# 12.net
KiCad netlist of a schematic drawn in Altium Designer
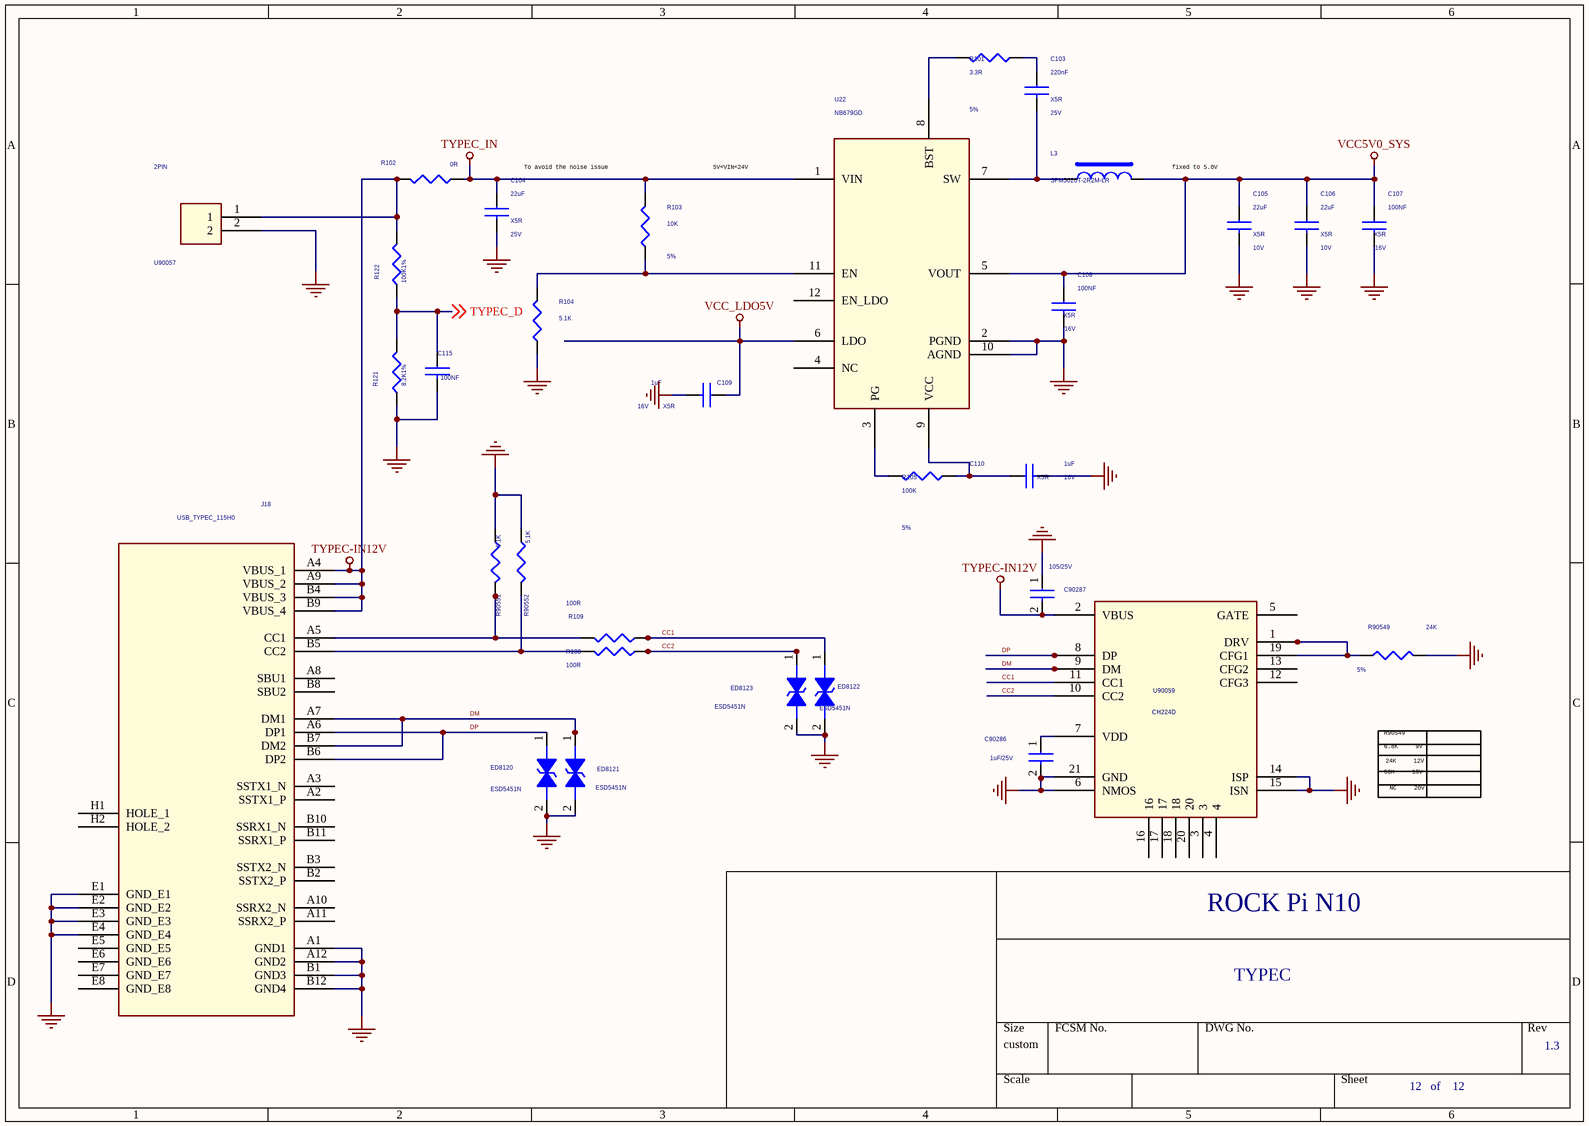
[diagram p0: 12.SchDoc]

(export (version "E")
  (design (tool "Eeschema 10.0.6"))
  (components
    (comp (ref "C103")
      (value "220nF")
      (footprint "C0402")
      (description "cap,220.00nF,+/-10%,25V,X5R,C0402")
      (fields
        (field (name "DIELECTRIC") "X5R")
        (field (name "VOLTAGE") "25V")
        (field (name "MANUFACTURER") "TDK")
        (field (name "TOLERANCE") "10%")
        (field (name "CREATED BY") "JJJ")
      )
      (libsource (lib "*") (part "CAP NP_2"))
    )
    (comp (ref "C104")
      (value "22uF")
      (footprint "C0805")
      (description "cap,10.00uF,+/-10%,16V,X5R,C0805")
      (fields
        (field (name "DIELECTRIC") "X5R")
        (field (name "VOLTAGE") "25V")
        (field (name "TOLERANCE") "10%")
        (field (name "MANUFACTURER") "TDK")
        (field (name "CREATED BY") "JJJ")
      )
      (libsource (lib "*") (part "CAP NP_2"))
    )
    (comp (ref "C105")
      (value "22uF")
      (footprint "C0603")
      (description "cap,22.00uF,+/-10%,10V,X5R,C0805")
      (fields
        (field (name "DIELECTRIC") "X5R")
        (field (name "VOLTAGE") "10V")
        (field (name "TOLERANCE") "10%")
        (field (name "MANUFACTURER") "TDK")
        (field (name "CREATED BY") "JJJ")
      )
      (libsource (lib "*") (part "CAP NP_2"))
    )
    (comp (ref "C106")
      (value "22uF")
      (footprint "C0603")
      (description "cap,22.00uF,+/-10%,10V,X5R,C0805")
      (fields
        (field (name "DIELECTRIC") "X5R")
        (field (name "VOLTAGE") "10V")
        (field (name "TOLERANCE") "10%")
        (field (name "MANUFACTURER") "TDK")
        (field (name "CREATED BY") "JJJ")
      )
      (libsource (lib "*") (part "CAP NP_2"))
    )
    (comp (ref "C107")
      (value "100NF")
      (footprint "C0402")
      (description "cap,100.00nF,+/-10%,16V,X5R,C0402")
      (fields
        (field (name "DIELECTRIC") "X5R")
        (field (name "VOLTAGE") "16V")
        (field (name "MANUFACTURER") "TDK")
        (field (name "TOLERANCE") "10%")
        (field (name "CREATED BY") "JJJ")
      )
      (libsource (lib "*") (part "CAP NP_2"))
    )
    (comp (ref "C108")
      (value "100NF")
      (footprint "C0402")
      (description "cap,100.00nF,+/-10%,16V,X5R,C0402")
      (fields
        (field (name "DIELECTRIC") "X5R")
        (field (name "VOLTAGE") "16V")
        (field (name "TOLERANCE") "10%")
        (field (name "MANUFACTURER") "TDK")
        (field (name "CREATED BY") "JJJ")
      )
      (libsource (lib "*") (part "CAP NP_2"))
    )
    (comp (ref "C109")
      (value "1uF")
      (footprint "C0402")
      (description "cap,1.00uF,+/-10%,16V,X5R,C0402")
      (fields
        (field (name "DIELECTRIC") "X5R")
        (field (name "VOLTAGE") "16V")
        (field (name "MANUFACTURER") "TDK")
        (field (name "TOLERANCE") "10%")
        (field (name "CREATED BY") "JJJ")
      )
      (libsource (lib "*") (part "CAP NP_2"))
    )
    (comp (ref "C110")
      (value "1uF")
      (footprint "C0402")
      (description "cap,1.00uF,+/-10%,16V,X5R,C0402")
      (fields
        (field (name "DIELECTRIC") "X5R")
        (field (name "VOLTAGE") "16V")
        (field (name "TOLERANCE") "10%")
        (field (name "MANUFACTURER") "TDK")
        (field (name "CREATED BY") "JJJ")
      )
      (libsource (lib "*") (part "CAP NP_2"))
    )
    (comp (ref "C115")
      (value "100NF")
      (footprint "C0402")
      (description "cap,100.00nF,+/-10%,16V,X5R,C0402")
      (fields
        (field (name "VOLTAGE") "16V")
        (field (name "MANUFACTURER") "TDK")
        (field (name "CREATED BY") "JJJ")
      )
      (libsource (lib "*") (part "CAP NP_2"))
    )
    (comp (ref "C90286")
      (value "1uF/25V")
      (footprint "C0603")
      (description "cap,1.00uF,+/-10%,16V,X5R,C0402")
      (fields
        (field (name "VOLTAGE") "16V")
        (field (name "MANUFACTURER") "TDK")
        (field (name "CREATED BY") "JJJ")
      )
      (libsource (lib "*") (part "CAP NP"))
    )
    (comp (ref "C90287")
      (value "105/25V")
      (footprint "C0402")
      (description "cap,1.00uF,+/-10%,16V,X5R,C0402")
      (fields
        (field (name "VOLTAGE") "25V")
        (field (name "TOLERANCE") "10%")
        (field (name "CREATED BY") "JJJ")
      )
      (libsource (lib "*") (part "CAP NP"))
    )
    (comp (ref "ED8120")
      (value "ESD5451N")
      (footprint "E0402N")
      (description "1-Line, Bi-directional, Transient Voltage Suppressors.17.5pF.")
      (fields (field (name "MANUFACTURER") "WillSemi(韦尔半导体)") (field (name "CREATED BY") "JJJ"))
      (libsource (lib "*") (part "DIODE BI_DIR TRIG"))
    )
    (comp (ref "ED8121")
      (value "ESD5451N")
      (footprint "E0402N")
      (description "1-Line, Bi-directional, Transient Voltage Suppressors.17.5pF.")
      (fields (field (name "MANUFACTURER") "WillSemi(韦尔半导体)") (field (name "CREATED BY") "JJJ"))
      (libsource (lib "*") (part "DIODE BI_DIR TRIG"))
    )
    (comp (ref "ED8122")
      (value "ESD5451N")
      (footprint "E0402N")
      (description "1-Line, Bi-directional, Transient Voltage Suppressors.17.5pF.")
      (fields (field (name "MANUFACTURER") "WillSemi(韦尔半导体)") (field (name "CREATED BY") "JJJ"))
      (libsource (lib "*") (part "DIODE BI_DIR TRIG"))
    )
    (comp (ref "ED8123")
      (value "ESD5451N")
      (footprint "E0402N")
      (description "1-Line, Bi-directional, Transient Voltage Suppressors.17.5pF.")
      (fields (field (name "MANUFACTURER") "WillSemi(韦尔半导体)") (field (name "CREATED BY") "JJJ"))
      (libsource (lib "*") (part "DIODE BI_DIR TRIG"))
    )
    (comp (ref "J18")
      (value "USB_TYPEC_115H0")
      (footprint "TYPEC-16PIN-GY")
      (description "USB Type-C 连接座")
      (fields (field (name "MANUFACTURER") "泰科") (field (name "CREATED BY") "JJJ"))
      (libsource (lib "*") (part "USB31_TYPE_C"))
    )
    (comp (ref "L3")
      (value "SPM5020T-2R2M-LR")
      (footprint "IND-5020")
      (libsource (lib "*") (part "INDUCTORS OF FERRITE"))
    )
    (comp (ref "R101")
      (value "3.3R")
      (footprint "R0402")
      (description "通用厚膜电阻,3R3,+/-5%,R0402,1/16W.")
      (fields
        (field (name "TOLERANCE") "5%")
        (field (name "MANUFACTURER") "YAGEO")
        (field (name "CREATED BY") "YTL")
      )
      (libsource (lib "*") (part "RESISTOR_3"))
    )
    (comp (ref "R102")
      (value "0R")
      (footprint "R1206")
      (description "SMD  1206  0R  1/4W  ±1%  ROHS")
      (libsource (lib "*") (part "R_0"))
    )
    (comp (ref "R103")
      (value "10K")
      (footprint "R0402")
      (description "通用厚膜电阻,10K,+/-5%,R0402,1/16W.")
      (fields
        (field (name "TOLERANCE") "5%")
        (field (name "MANUFACTURER") "YAGEO")
        (field (name "CREATED BY") "YTL")
      )
      (libsource (lib "*") (part "RESISTOR_3"))
    )
    (comp (ref "R104")
      (value "5.1K")
      (footprint "R0402")
      (description "通用厚膜电阻,10K,+/-5%,R0402,1/16W.")
      (fields
        (field (name "TOLERANCE") "5%")
        (field (name "MANUFACTURER") "YAGEO")
        (field (name "CREATED BY") "YTL")
      )
      (libsource (lib "*") (part "RESISTOR_3"))
    )
    (comp (ref "R105")
      (value "100K")
      (footprint "R0402")
      (description "通用厚膜电阻,100K,+/-5%,R0402,1/16W.")
      (fields
        (field (name "TOLERANCE") "5%")
        (field (name "MANUFACTURER") "YAGEO")
        (field (name "CREATED BY") "YTL")
      )
      (libsource (lib "*") (part "RESISTOR_3"))
    )
    (comp (ref "R108")
      (value "100R")
      (footprint "R0402")
      (description "通用厚膜电阻,100K,+/-5%,R0402,1/16W.")
      (fields
        (field (name "TOLERANCE") "5%")
        (field (name "MANUFACTURER") "YAGEO")
        (field (name "CREATED BY") "YTL")
      )
      (libsource (lib "*") (part "RESISTOR_3"))
    )
    (comp (ref "R109")
      (value "100R")
      (footprint "R0402")
      (description "通用厚膜电阻,100K,+/-5%,R0402,1/16W.")
      (fields
        (field (name "TOLERANCE") "5%")
        (field (name "MANUFACTURER") "YAGEO")
        (field (name "CREATED BY") "YTL")
      )
      (libsource (lib "*") (part "RESISTOR_3"))
    )
    (comp (ref "R121")
      (value "8.2K1%")
      (footprint "R0402")
      (description "通用厚膜电阻,8.2K,+/-1%,R0402,1/16W.")
      (fields
        (field (name "TOLERANCE") "5%")
        (field (name "MANUFACTURER") "YAGEO")
        (field (name "CREATED BY") "YTL")
      )
      (libsource (lib "*") (part "RESISTOR_3"))
    )
    (comp (ref "R122")
      (value "100K1%")
      (footprint "R0402")
      (description "通用厚膜电阻,100K,+/-1%,R0402,1/16W.")
      (fields
        (field (name "TOLERANCE") "5%")
        (field (name "MANUFACTURER") "YAGEO")
        (field (name "CREATED BY") "YTL")
      )
      (libsource (lib "*") (part "RESISTOR_3"))
    )
    (comp (ref "R90549")
      (value "24K")
      (footprint "R0402")
      (description "通用厚膜电阻,10K,+/-5%,R0402,1/16W.")
      (fields
        (field (name "TOLERANCE") "5%")
        (field (name "MANUFACTURER") "YAGEO")
        (field (name "CREATED BY") "YTL")
      )
      (libsource (lib "*") (part "RESISTOR_2"))
    )
    (comp (ref "R90551")
      (value "5.1K")
      (footprint "R0402")
      (description "通用厚膜电阻,10K,+/-5%,R0402,1/16W.")
      (fields
        (field (name "TOLERANCE") "5%")
        (field (name "MANUFACTURER") "YAGEO")
        (field (name "CREATED BY") "YTL")
      )
      (libsource (lib "*") (part "RESISTOR_2"))
    )
    (comp (ref "R90552")
      (value "5.1K")
      (footprint "R0402")
      (description "通用厚膜电阻,10K,+/-5%,R0402,1/16W.")
      (fields
        (field (name "TOLERANCE") "5%")
        (field (name "MANUFACTURER") "YAGEO")
        (field (name "CREATED BY") "YTL")
      )
      (libsource (lib "*") (part "RESISTOR_2"))
    )
    (comp (ref "U22")
      (value "NB679GD")
      (footprint "QFN12_3R00X2R00X0R90")
      (description "26 V, Low Iq, High Current, Fixed 5 V-8 A Synchronous Buck Converter with 100 mA LDO;")
      (fields (field (name "MANUFACTURER") "MPS （美国芯源）") (field (name "CREATED BY") "JJJ"))
      (libsource (lib "*") (part "DCDC_NB679"))
    )
    (comp (ref "U90057") (value "2PIN") (footprint "2PIN_2_54") (libsource (lib "*") (part "2PIN")))
    (comp (ref "U90059") (value "CH224D") (footprint "CH224D") (libsource (lib "*") (part "CH224D")))
  )
  (nets
    (net (code "1") (name "/CC1") (class "Default")
      (node (ref "ED8122") (pin "1") (pinfunction "1_1") (pintype "passive"))
      (node (ref "R109") (pin "2") (pinfunction "2_2") (pintype "passive"))
      (node (ref "U90059") (pin "11") (pinfunction "CC1_11") (pintype "passive"))
    )
    (net (code "2") (name "/CC2") (class "Default")
      (node (ref "ED8123") (pin "1") (pinfunction "1_1") (pintype "passive"))
      (node (ref "R108") (pin "2") (pinfunction "2_2") (pintype "passive"))
      (node (ref "U90059") (pin "10") (pinfunction "CC2_10") (pintype "passive"))
    )
    (net (code "3") (name "/DM") (class "Default")
      (node (ref "ED8121") (pin "1") (pinfunction "1_1") (pintype "passive"))
      (node (ref "J18") (pin "A7") (pinfunction "DM1_A7") (pintype "passive"))
      (node (ref "J18") (pin "B7") (pinfunction "DM2_B7") (pintype "passive"))
      (node (ref "U90059") (pin "9") (pinfunction "DM_9") (pintype "passive"))
    )
    (net (code "4") (name "/DP") (class "Default")
      (node (ref "ED8120") (pin "1") (pinfunction "1_1") (pintype "passive"))
      (node (ref "J18") (pin "A6") (pinfunction "DP1_A6") (pintype "passive"))
      (node (ref "J18") (pin "B6") (pinfunction "DP2_B6") (pintype "passive"))
      (node (ref "U90059") (pin "8") (pinfunction "DP_8") (pintype "passive"))
    )
    (net (code "5") (name "GND") (class "Default")
      (node (ref "C104") (pin "2") (pinfunction "2_2") (pintype "passive"))
      (node (ref "C105") (pin "2") (pinfunction "2_2") (pintype "passive"))
      (node (ref "C106") (pin "2") (pinfunction "2_2") (pintype "passive"))
      (node (ref "C107") (pin "2") (pinfunction "2_2") (pintype "passive"))
      (node (ref "C108") (pin "2") (pinfunction "2_2") (pintype "passive"))
      (node (ref "C109") (pin "2") (pinfunction "2_2") (pintype "passive"))
      (node (ref "C110") (pin "2") (pinfunction "2_2") (pintype "passive"))
      (node (ref "C115") (pin "2") (pinfunction "2_2") (pintype "passive"))
      (node (ref "C90286") (pin "2") (pinfunction "2_2") (pintype "passive"))
      (node (ref "C90287") (pin "1") (pinfunction "1_1") (pintype "passive"))
      (node (ref "ED8120") (pin "2") (pinfunction "2_2") (pintype "passive"))
      (node (ref "ED8121") (pin "2") (pinfunction "2_2") (pintype "passive"))
      (node (ref "ED8122") (pin "2") (pinfunction "2_2") (pintype "passive"))
      (node (ref "ED8123") (pin "2") (pinfunction "2_2") (pintype "passive"))
      (node (ref "J18") (pin "A1") (pinfunction "GND1_A1") (pintype "passive"))
      (node (ref "J18") (pin "A12") (pinfunction "GND2_A12") (pintype "passive"))
      (node (ref "J18") (pin "B1") (pinfunction "GND3_B1") (pintype "passive"))
      (node (ref "J18") (pin "B12") (pinfunction "GND4_B12") (pintype "passive"))
      (node (ref "J18") (pin "E1") (pinfunction "GND_E1_E1") (pintype "passive"))
      (node (ref "J18") (pin "E2") (pinfunction "GND_E2_E2") (pintype "passive"))
      (node (ref "J18") (pin "E3") (pinfunction "GND_E3_E3") (pintype "passive"))
      (node (ref "J18") (pin "E4") (pinfunction "GND_E4_E4") (pintype "passive"))
      (node (ref "R104") (pin "1") (pinfunction "1_1") (pintype "passive"))
      (node (ref "R121") (pin "1") (pinfunction "1_1") (pintype "passive"))
      (node (ref "R90549") (pin "1") (pinfunction "1_1") (pintype "passive"))
      (node (ref "R90551") (pin "1") (pinfunction "1_1") (pintype "passive"))
      (node (ref "R90552") (pin "1") (pinfunction "1_1") (pintype "passive"))
      (node (ref "U22") (pin "10") (pinfunction "AGND_10") (pintype "passive"))
      (node (ref "U22") (pin "2") (pinfunction "PGND_2") (pintype "passive"))
      (node (ref "U90057") (pin "2") (pinfunction "2_2") (pintype "passive"))
      (node (ref "U90059") (pin "14") (pinfunction "ISP_14") (pintype "passive"))
      (node (ref "U90059") (pin "15") (pinfunction "ISN_15") (pintype "passive"))
      (node (ref "U90059") (pin "21") (pinfunction "GND_21") (pintype "passive"))
      (node (ref "U90059") (pin "6") (pinfunction "NMOS_6") (pintype "passive"))
    )
    (net (code "6") (name "Net-(C103-Pad1)") (class "Default")
      (node (ref "C103") (pin "1") (pinfunction "1_1") (pintype "passive"))
      (node (ref "R101") (pin "2") (pinfunction "2_2") (pintype "passive"))
    )
    (net (code "7") (name "Net-(J18-CC1)") (class "Default")
      (node (ref "J18") (pin "A5") (pinfunction "CC1_A5") (pintype "passive"))
      (node (ref "R109") (pin "1") (pinfunction "1_1") (pintype "passive"))
      (node (ref "R90551") (pin "2") (pinfunction "2_2") (pintype "passive"))
    )
    (net (code "8") (name "Net-(J18-CC2)") (class "Default")
      (node (ref "J18") (pin "B5") (pinfunction "CC2_B5") (pintype "passive"))
      (node (ref "R108") (pin "1") (pinfunction "1_1") (pintype "passive"))
      (node (ref "R90552") (pin "2") (pinfunction "2_2") (pintype "passive"))
    )
    (net (code "9") (name "Net-(U22-BST)") (class "Default")
      (node (ref "R101") (pin "1") (pinfunction "1_1") (pintype "passive"))
      (node (ref "U22") (pin "8") (pinfunction "BST_8") (pintype "passive"))
    )
    (net (code "10") (name "Net-(U22-EN)") (class "Default")
      (node (ref "R103") (pin "1") (pinfunction "1_1") (pintype "passive"))
      (node (ref "R104") (pin "2") (pinfunction "2_2") (pintype "passive"))
      (node (ref "U22") (pin "11") (pinfunction "EN_11") (pintype "passive"))
    )
    (net (code "11") (name "Net-(U22-PG)") (class "Default")
      (node (ref "R105") (pin "1") (pinfunction "1_1") (pintype "passive"))
      (node (ref "U22") (pin "3") (pinfunction "PG_3") (pintype "passive"))
    )
    (net (code "12") (name "Net-(U22-SW)") (class "Default")
      (node (ref "C103") (pin "2") (pinfunction "2_2") (pintype "passive"))
      (node (ref "L3") (pin "1") (pinfunction "1_1") (pintype "passive"))
      (node (ref "U22") (pin "7") (pinfunction "SW_7") (pintype "passive"))
    )
    (net (code "13") (name "Net-(U22-VCC)") (class "Default")
      (node (ref "C110") (pin "1") (pinfunction "1_1") (pintype "passive"))
      (node (ref "R105") (pin "2") (pinfunction "2_2") (pintype "passive"))
      (node (ref "U22") (pin "9") (pinfunction "VCC_9") (pintype "passive"))
    )
    (net (code "14") (name "Net-(U90059-CFG1)") (class "Default")
      (node (ref "R90549") (pin "2") (pinfunction "2_2") (pintype "passive"))
      (node (ref "U90059") (pin "1") (pinfunction "DRV_1") (pintype "passive"))
      (node (ref "U90059") (pin "19") (pinfunction "CFG1_19") (pintype "passive"))
    )
    (net (code "15") (name "Net-(U90059-VDD)") (class "Default")
      (node (ref "C90286") (pin "1") (pinfunction "1_1") (pintype "passive"))
      (node (ref "U90059") (pin "7") (pinfunction "VDD_7") (pintype "passive"))
    )
    (net (code "16") (name "TYPEC-IN12V") (class "Default")
      (node (ref "C90287") (pin "2") (pinfunction "2_2") (pintype "passive"))
      (node (ref "J18") (pin "A4") (pinfunction "VBUS_1_A4") (pintype "passive"))
      (node (ref "J18") (pin "A9") (pinfunction "VBUS_2_A9") (pintype "passive"))
      (node (ref "J18") (pin "B4") (pinfunction "VBUS_3_B4") (pintype "passive"))
      (node (ref "J18") (pin "B9") (pinfunction "VBUS_4_B9") (pintype "passive"))
      (node (ref "R102") (pin "2") (pinfunction "2_2") (pintype "passive"))
      (node (ref "R122") (pin "2") (pinfunction "2_2") (pintype "passive"))
      (node (ref "U90057") (pin "1") (pinfunction "1_1") (pintype "passive"))
      (node (ref "U90059") (pin "2") (pinfunction "VBUS_2") (pintype "passive"))
    )
    (net (code "17") (name "TYPEC_D") (class "Default")
      (node (ref "C115") (pin "1") (pinfunction "1_1") (pintype "passive"))
      (node (ref "R121") (pin "2") (pinfunction "2_2") (pintype "passive"))
      (node (ref "R122") (pin "1") (pinfunction "1_1") (pintype "passive"))
    )
    (net (code "18") (name "TYPEC_IN") (class "Default")
      (node (ref "C104") (pin "1") (pinfunction "1_1") (pintype "passive"))
      (node (ref "R102") (pin "1") (pinfunction "1_1") (pintype "passive"))
      (node (ref "R103") (pin "2") (pinfunction "2_2") (pintype "passive"))
      (node (ref "U22") (pin "1") (pinfunction "VIN_1") (pintype "passive"))
    )
    (net (code "19") (name "VCC5V0_SYS") (class "Default")
      (node (ref "C105") (pin "1") (pinfunction "1_1") (pintype "passive"))
      (node (ref "C106") (pin "1") (pinfunction "1_1") (pintype "passive"))
      (node (ref "C107") (pin "1") (pinfunction "1_1") (pintype "passive"))
      (node (ref "C108") (pin "1") (pinfunction "1_1") (pintype "passive"))
      (node (ref "L3") (pin "2") (pinfunction "2_2") (pintype "passive"))
      (node (ref "U22") (pin "5") (pinfunction "VOUT_5") (pintype "passive"))
    )
    (net (code "20") (name "VCC_LDO5V") (class "Default")
      (node (ref "C109") (pin "1") (pinfunction "1_1") (pintype "passive"))
      (node (ref "U22") (pin "6") (pinfunction "LDO_6") (pintype "passive"))
    )
    (net (code "21") (name "unconnected-(J18-GND_E5-PadE5)") (class "Default")
      (node (ref "J18") (pin "E5") (pinfunction "GND_E5_E5") (pintype "passive"))
    )
    (net (code "22") (name "unconnected-(J18-GND_E6-PadE6)") (class "Default")
      (node (ref "J18") (pin "E6") (pinfunction "GND_E6_E6") (pintype "passive"))
    )
    (net (code "23") (name "unconnected-(J18-GND_E7-PadE7)") (class "Default")
      (node (ref "J18") (pin "E7") (pinfunction "GND_E7_E7") (pintype "passive"))
    )
    (net (code "24") (name "unconnected-(J18-GND_E8-PadE8)") (class "Default")
      (node (ref "J18") (pin "E8") (pinfunction "GND_E8_E8") (pintype "passive"))
    )
    (net (code "25") (name "unconnected-(J18-HOLE_1-PadH1)") (class "Default")
      (node (ref "J18") (pin "H1") (pinfunction "HOLE_1_H1") (pintype "passive"))
    )
    (net (code "26") (name "unconnected-(J18-HOLE_2-PadH2)") (class "Default")
      (node (ref "J18") (pin "H2") (pinfunction "HOLE_2_H2") (pintype "passive"))
    )
    (net (code "27") (name "unconnected-(J18-SBU1-PadA8)") (class "Default")
      (node (ref "J18") (pin "A8") (pinfunction "SBU1_A8") (pintype "passive"))
    )
    (net (code "28") (name "unconnected-(J18-SBU2-PadB8)") (class "Default")
      (node (ref "J18") (pin "B8") (pinfunction "SBU2_B8") (pintype "passive"))
    )
    (net (code "29") (name "unconnected-(J18-SSRX1_N-PadB10)") (class "Default")
      (node (ref "J18") (pin "B10") (pinfunction "SSRX1_N_B10") (pintype "passive"))
    )
    (net (code "30") (name "unconnected-(J18-SSRX1_P-PadB11)") (class "Default")
      (node (ref "J18") (pin "B11") (pinfunction "SSRX1_P_B11") (pintype "passive"))
    )
    (net (code "31") (name "unconnected-(J18-SSRX2_N-PadA10)") (class "Default")
      (node (ref "J18") (pin "A10") (pinfunction "SSRX2_N_A10") (pintype "passive"))
    )
    (net (code "32") (name "unconnected-(J18-SSRX2_P-PadA11)") (class "Default")
      (node (ref "J18") (pin "A11") (pinfunction "SSRX2_P_A11") (pintype "passive"))
    )
    (net (code "33") (name "unconnected-(J18-SSTX1_N-PadA3)") (class "Default")
      (node (ref "J18") (pin "A3") (pinfunction "SSTX1_N_A3") (pintype "passive"))
    )
    (net (code "34") (name "unconnected-(J18-SSTX1_P-PadA2)") (class "Default")
      (node (ref "J18") (pin "A2") (pinfunction "SSTX1_P_A2") (pintype "passive"))
    )
    (net (code "35") (name "unconnected-(J18-SSTX2_N-PadB3)") (class "Default")
      (node (ref "J18") (pin "B3") (pinfunction "SSTX2_N_B3") (pintype "passive"))
    )
    (net (code "36") (name "unconnected-(J18-SSTX2_P-PadB2)") (class "Default")
      (node (ref "J18") (pin "B2") (pinfunction "SSTX2_P_B2") (pintype "passive"))
    )
    (net (code "37") (name "unconnected-(U22-EN_LDO-Pad12)") (class "Default")
      (node (ref "U22") (pin "12") (pinfunction "EN_LDO_12") (pintype "passive"))
    )
    (net (code "38") (name "unconnected-(U22-NC-Pad4)") (class "Default")
      (node (ref "U22") (pin "4") (pinfunction "NC_4") (pintype "passive"))
    )
    (net (code "39") (name "unconnected-(U90059-CFG2-Pad13)") (class "Default")
      (node (ref "U90059") (pin "13") (pinfunction "CFG2_13") (pintype "passive"))
    )
    (net (code "40") (name "unconnected-(U90059-CFG3-Pad12)") (class "Default")
      (node (ref "U90059") (pin "12") (pinfunction "CFG3_12") (pintype "passive"))
    )
    (net (code "41") (name "unconnected-(U90059-GATE-Pad5)") (class "Default")
      (node (ref "U90059") (pin "5") (pinfunction "GATE_5") (pintype "passive"))
    )
    (net (code "42") (name "unconnected-(U90059-Pad3)") (class "Default")
      (node (ref "U90059") (pin "3") (pinfunction "3_3") (pintype "passive"))
    )
    (net (code "43") (name "unconnected-(U90059-Pad4)") (class "Default")
      (node (ref "U90059") (pin "4") (pinfunction "4_4") (pintype "passive"))
    )
    (net (code "44") (name "unconnected-(U90059-Pad16)") (class "Default")
      (node (ref "U90059") (pin "16") (pinfunction "16_16") (pintype "passive"))
    )
    (net (code "45") (name "unconnected-(U90059-Pad17)") (class "Default")
      (node (ref "U90059") (pin "17") (pinfunction "17_17") (pintype "passive"))
    )
    (net (code "46") (name "unconnected-(U90059-Pad18)") (class "Default")
      (node (ref "U90059") (pin "18") (pinfunction "18_18") (pintype "passive"))
    )
    (net (code "47") (name "unconnected-(U90059-Pad20)") (class "Default")
      (node (ref "U90059") (pin "20") (pinfunction "20_20") (pintype "passive"))
    )
  )
)
